# MCU.net
KiCad netlist of a schematic drawn in Altium Designer
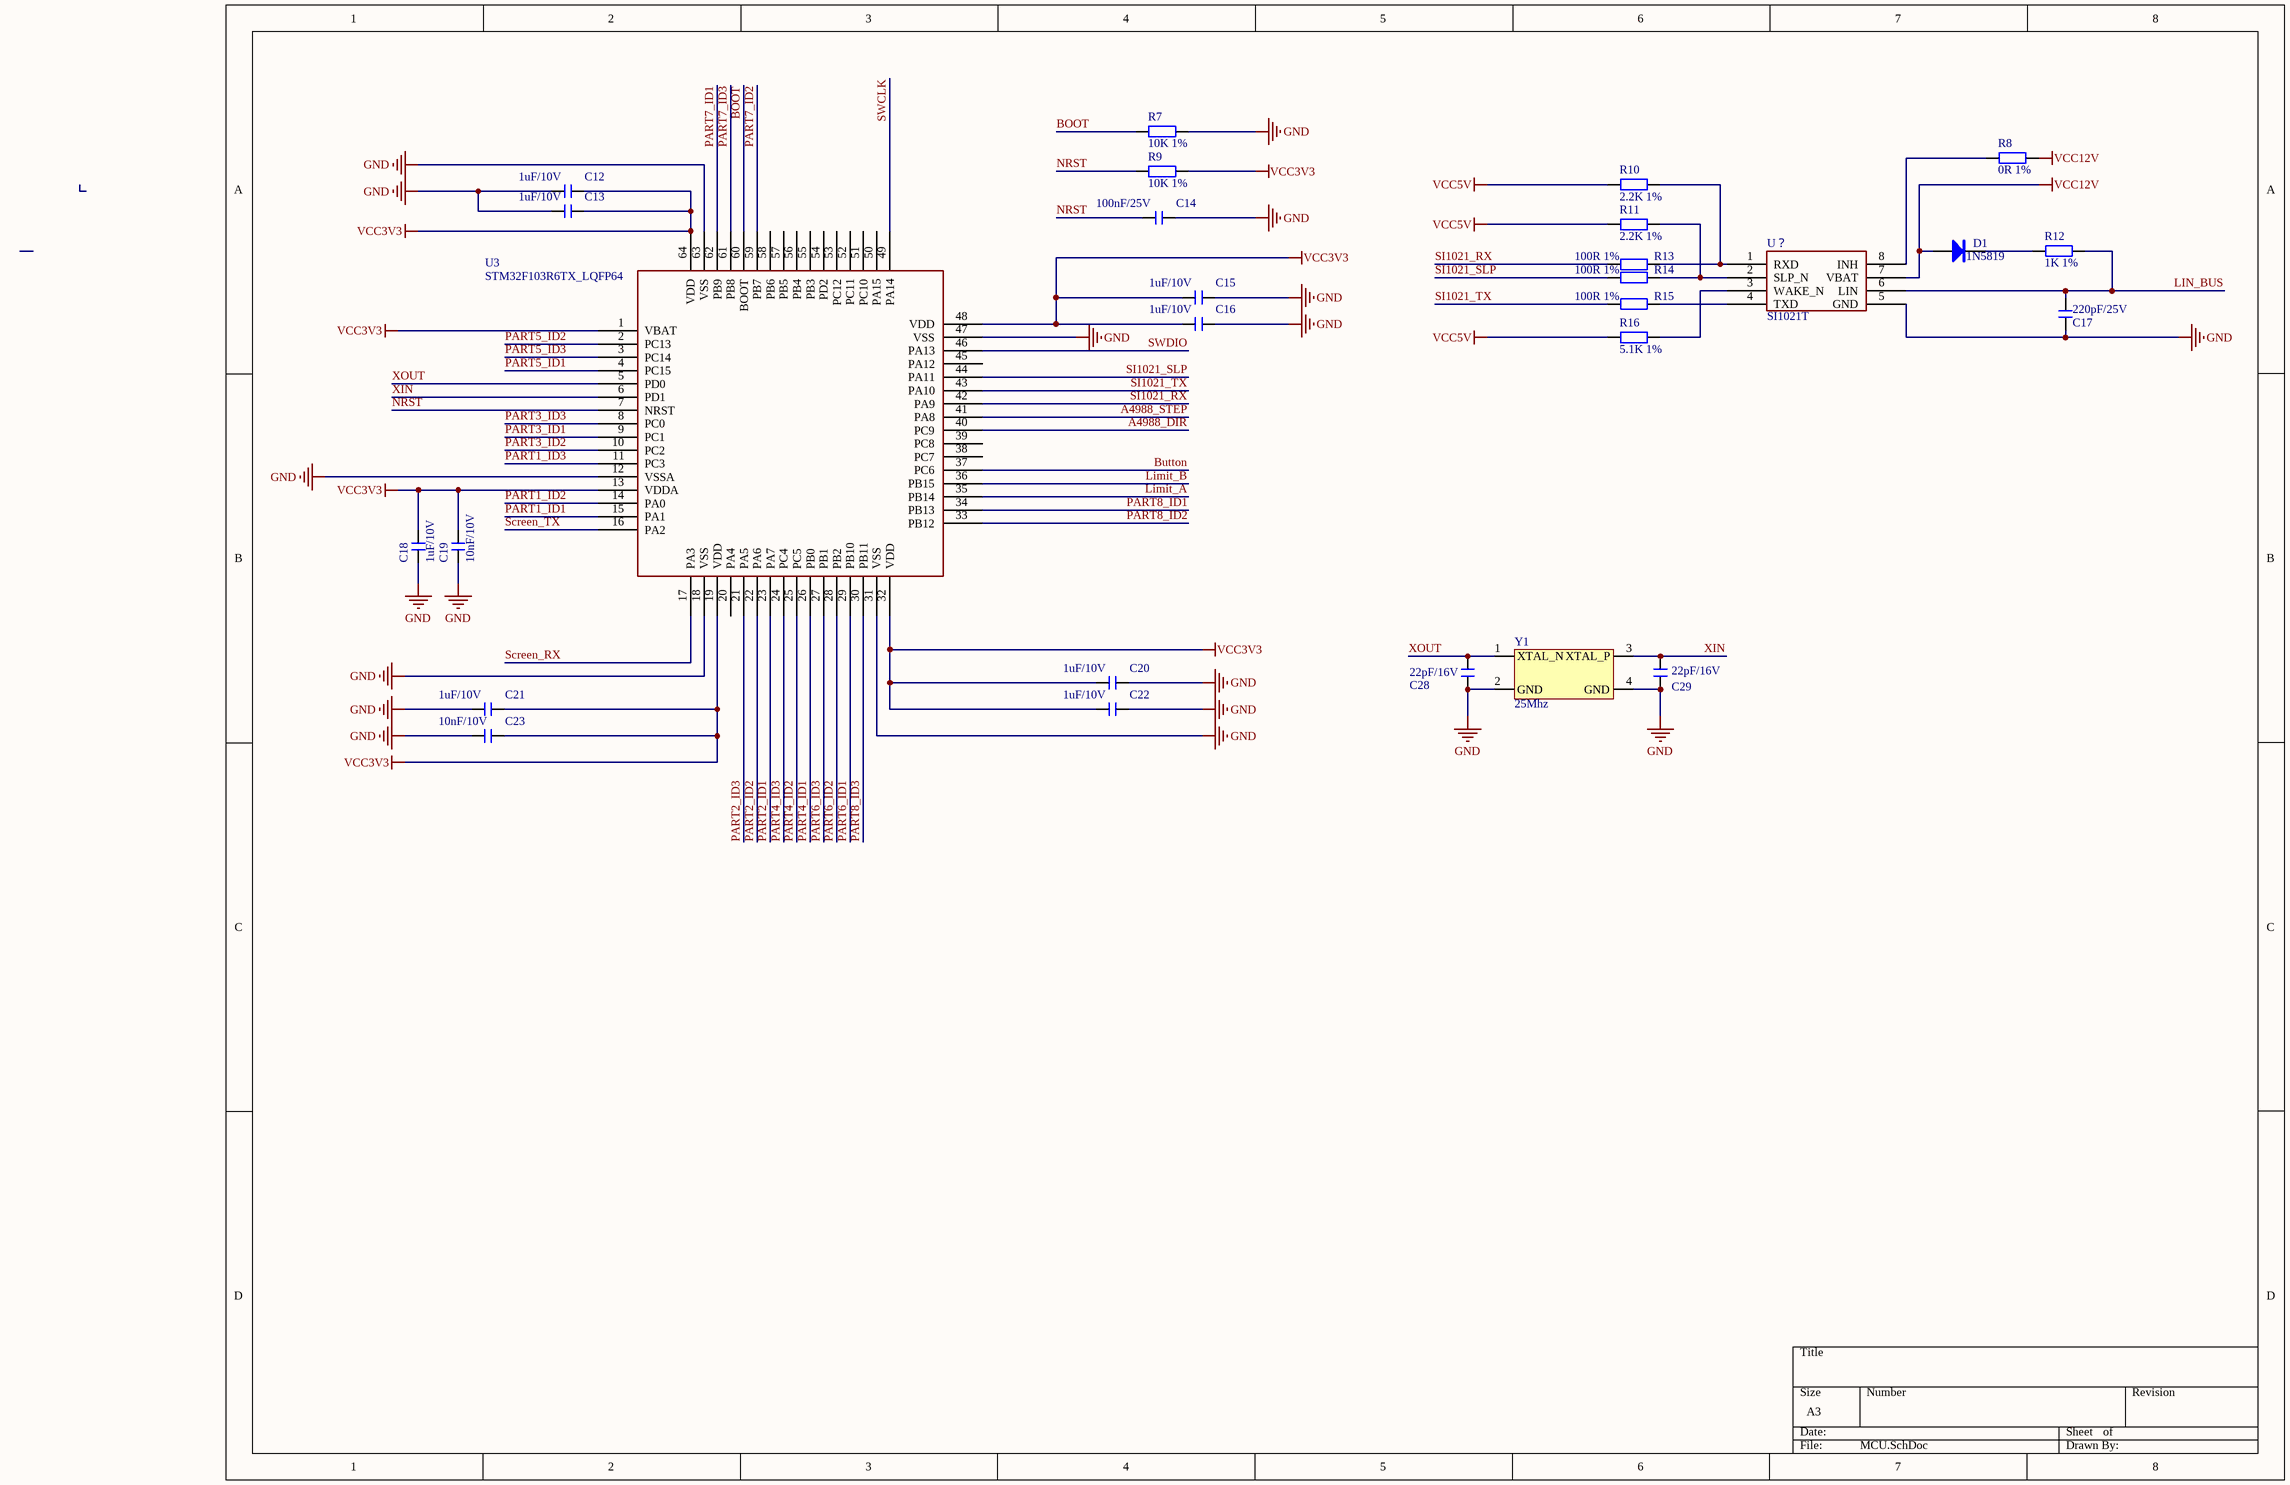
[diagram p0: MCU.SchDoc]

(export (version "E")
  (design (tool "Eeschema 10.0.6"))
  (components
    (comp (ref "C12")
      (value "1uF/10V")
      (footprint "C0603_L")
      (description "无极性贴片电容")
      (fields (field (name "版权归属") "源创客"))
      (libsource (lib "Capacitor") (part "C"))
    )
    (comp (ref "C13")
      (value "1uF/10V")
      (footprint "C0603_L")
      (description "无极性贴片电容")
      (fields (field (name "版权归属") "源创客"))
      (libsource (lib "Capacitor") (part "C"))
    )
    (comp (ref "C14")
      (value "100nF/25V")
      (footprint "C0603_L")
      (description "无极性贴片电容")
      (fields (field (name "版权归属") "源创客"))
      (libsource (lib "Capacitor") (part "C"))
    )
    (comp (ref "C15")
      (value "1uF/10V")
      (footprint "C0603_L")
      (description "无极性贴片电容")
      (fields (field (name "版权归属") "源创客"))
      (libsource (lib "Capacitor") (part "C"))
    )
    (comp (ref "C16")
      (value "1uF/10V")
      (footprint "C0603_L")
      (description "无极性贴片电容")
      (fields (field (name "版权归属") "源创客"))
      (libsource (lib "Capacitor") (part "C"))
    )
    (comp (ref "C17")
      (value "220pF/25V")
      (footprint "C0603_L")
      (description "无极性贴片电容")
      (fields (field (name "版权归属") "源创客"))
      (libsource (lib "Capacitor") (part "C"))
    )
    (comp (ref "C18")
      (value "1uF/10V")
      (footprint "C0603_L")
      (description "无极性贴片电容")
      (fields (field (name "版权归属") "源创客"))
      (libsource (lib "Capacitor") (part "C"))
    )
    (comp (ref "C19")
      (value "10nF/10V")
      (footprint "C0603_L")
      (description "无极性贴片电容")
      (fields (field (name "版权归属") "源创客"))
      (libsource (lib "Capacitor") (part "C"))
    )
    (comp (ref "C20")
      (value "1uF/10V")
      (footprint "C0603_L")
      (description "无极性贴片电容")
      (fields (field (name "版权归属") "源创客"))
      (libsource (lib "Capacitor") (part "C"))
    )
    (comp (ref "C21")
      (value "1uF/10V")
      (footprint "C0603_L")
      (description "无极性贴片电容")
      (fields (field (name "版权归属") "源创客"))
      (libsource (lib "Capacitor") (part "C"))
    )
    (comp (ref "C22")
      (value "1uF/10V")
      (footprint "C0603_L")
      (description "无极性贴片电容")
      (fields (field (name "版权归属") "源创客"))
      (libsource (lib "Capacitor") (part "C"))
    )
    (comp (ref "C23")
      (value "10nF/10V")
      (footprint "C0603_L")
      (description "无极性贴片电容")
      (fields (field (name "版权归属") "源创客"))
      (libsource (lib "Capacitor") (part "C"))
    )
    (comp (ref "C28")
      (value "22pF/16V")
      (footprint "C0402_L")
      (description "无极性贴片电容")
      (fields (field (name "版权归属") "源创客"))
      (libsource (lib "Capacitor") (part "C"))
    )
    (comp (ref "C29")
      (value "22pF/16V")
      (footprint "C0402_L")
      (description "无极性贴片电容")
      (fields (field (name "版权归属") "源创客"))
      (libsource (lib "Capacitor") (part "C"))
    )
    (comp (ref "D1")
      (value "1N5819")
      (footprint "SOD-323")
      (description "肖特基二极管")
      (fields (field (name "版权归属") "源创客"))
      (libsource (lib "Diode") (part "1N5819"))
    )
    (comp (ref "R7")
      (value "10K 1%")
      (footprint "R0603_L")
      (description "贴片电阻")
      (fields (field (name "版权归属") "源创客"))
      (libsource (lib "Resistor") (part "R"))
    )
    (comp (ref "R8")
      (value "0R 1%")
      (footprint "R0603_L")
      (description "贴片电阻")
      (fields (field (name "版权归属") "源创客"))
      (libsource (lib "Resistor") (part "R"))
    )
    (comp (ref "R9")
      (value "10K 1%")
      (footprint "R0603_L")
      (description "贴片电阻")
      (fields (field (name "版权归属") "源创客"))
      (libsource (lib "Resistor") (part "R"))
    )
    (comp (ref "R10")
      (value "2.2K 1%")
      (footprint "R0603_L")
      (description "贴片电阻")
      (fields (field (name "版权归属") "源创客"))
      (libsource (lib "Resistor") (part "R"))
    )
    (comp (ref "R11")
      (value "2.2K 1%")
      (footprint "R0603_L")
      (description "贴片电阻")
      (fields (field (name "版权归属") "源创客"))
      (libsource (lib "Resistor") (part "R"))
    )
    (comp (ref "R12")
      (value "1K 1%")
      (footprint "R0603_L")
      (description "贴片电阻")
      (fields (field (name "版权归属") "源创客"))
      (libsource (lib "Resistor") (part "R"))
    )
    (comp (ref "R13")
      (value "100R 1%")
      (footprint "R0603_L")
      (description "贴片电阻")
      (fields (field (name "版权归属") "源创客"))
      (libsource (lib "Resistor") (part "R"))
    )
    (comp (ref "R14")
      (value "100R 1%")
      (footprint "R0603_L")
      (description "贴片电阻")
      (fields (field (name "版权归属") "源创客"))
      (libsource (lib "Resistor") (part "R"))
    )
    (comp (ref "R15")
      (value "100R 1%")
      (footprint "R0603_L")
      (description "贴片电阻")
      (fields (field (name "版权归属") "源创客"))
      (libsource (lib "Resistor") (part "R"))
    )
    (comp (ref "R16")
      (value "5.1K 1%")
      (footprint "R0603_L")
      (description "贴片电阻")
      (fields (field (name "版权归属") "源创客"))
      (libsource (lib "Resistor") (part "R"))
    )
    (comp (ref "U3")
      (value "STM32F103R6TX_LQFP64")
      (footprint "LQFP64 10x10_N")
      (libsource (lib "MCU") (part "STM32F103R6TX_LQFP64"))
    )
    (comp (ref "U？")
      (value "SI1021T")
      (footprint "SOP8")
      (description "SI1021T LIN收发器")
      (libsource (lib "transceiver") (part "SI1021T"))
    )
    (comp (ref "Y1") (value "25Mhz") (footprint "OSC 3225-4P") (libsource (lib "Crystal") (part "Crystal")))
  )
  (nets
    (net (code "1") (name "/A4988_DIR") (class "Default")
      (node (ref "U3") (pin "40") (pinfunction "PC9_40") (pintype "passive"))
    )
    (net (code "2") (name "/A4988_STEP") (class "Default")
      (node (ref "U3") (pin "41") (pinfunction "PA8_41") (pintype "passive"))
    )
    (net (code "3") (name "/BOOT") (class "Default")
      (node (ref "R7") (pin "1") (pinfunction "1_1") (pintype "passive"))
      (node (ref "U3") (pin "60") (pinfunction "BOOT_60") (pintype "passive"))
    )
    (net (code "4") (name "/Button") (class "Default")
      (node (ref "U3") (pin "37") (pinfunction "PC6_37") (pintype "passive"))
    )
    (net (code "5") (name "/LIN_BUS") (class "Default")
      (node (ref "C17") (pin "2") (pinfunction "2_2") (pintype "passive"))
      (node (ref "R12") (pin "1") (pinfunction "1_1") (pintype "passive"))
      (node (ref "U？") (pin "6") (pinfunction "LIN_6") (pintype "passive"))
    )
    (net (code "6") (name "/Limit_A") (class "Default")
      (node (ref "U3") (pin "35") (pinfunction "PB14_35") (pintype "passive"))
    )
    (net (code "7") (name "/Limit_B") (class "Default")
      (node (ref "U3") (pin "36") (pinfunction "PB15_36") (pintype "passive"))
    )
    (net (code "8") (name "/NRST") (class "Default")
      (node (ref "C14") (pin "2") (pinfunction "2_2") (pintype "passive"))
      (node (ref "R9") (pin "1") (pinfunction "1_1") (pintype "passive"))
      (node (ref "U3") (pin "7") (pinfunction "NRST_7") (pintype "passive"))
    )
    (net (code "9") (name "/PART1_ID1") (class "Default")
      (node (ref "U3") (pin "15") (pinfunction "PA1_15") (pintype "passive"))
    )
    (net (code "10") (name "/PART1_ID2") (class "Default")
      (node (ref "U3") (pin "14") (pinfunction "PA0_14") (pintype "passive"))
    )
    (net (code "11") (name "/PART1_ID3") (class "Default")
      (node (ref "U3") (pin "11") (pinfunction "PC3_11") (pintype "passive"))
    )
    (net (code "12") (name "/PART2_ID1") (class "Default")
      (node (ref "U3") (pin "23") (pinfunction "PA7_23") (pintype "passive"))
    )
    (net (code "13") (name "/PART2_ID2") (class "Default")
      (node (ref "U3") (pin "22") (pinfunction "PA6_22") (pintype "passive"))
    )
    (net (code "14") (name "/PART2_ID3") (class "Default")
      (node (ref "U3") (pin "21") (pinfunction "PA5_21") (pintype "passive"))
    )
    (net (code "15") (name "/PART3_ID1") (class "Default")
      (node (ref "U3") (pin "9") (pinfunction "PC1_9") (pintype "passive"))
    )
    (net (code "16") (name "/PART3_ID2") (class "Default")
      (node (ref "U3") (pin "10") (pinfunction "PC2_10") (pintype "passive"))
    )
    (net (code "17") (name "/PART3_ID3") (class "Default")
      (node (ref "U3") (pin "8") (pinfunction "PC0_8") (pintype "passive"))
    )
    (net (code "18") (name "/PART4_ID1") (class "Default")
      (node (ref "U3") (pin "26") (pinfunction "PB0_26") (pintype "passive"))
    )
    (net (code "19") (name "/PART4_ID2") (class "Default")
      (node (ref "U3") (pin "25") (pinfunction "PC5_25") (pintype "passive"))
    )
    (net (code "20") (name "/PART4_ID3") (class "Default")
      (node (ref "U3") (pin "24") (pinfunction "PC4_24") (pintype "passive"))
    )
    (net (code "21") (name "/PART5_ID1") (class "Default")
      (node (ref "U3") (pin "4") (pinfunction "PC15_4") (pintype "passive"))
    )
    (net (code "22") (name "/PART5_ID2") (class "Default")
      (node (ref "U3") (pin "2") (pinfunction "PC13_2") (pintype "passive"))
    )
    (net (code "23") (name "/PART5_ID3") (class "Default")
      (node (ref "U3") (pin "3") (pinfunction "PC14_3") (pintype "passive"))
    )
    (net (code "24") (name "/PART6_ID1") (class "Default")
      (node (ref "U3") (pin "29") (pinfunction "PB10_29") (pintype "passive"))
    )
    (net (code "25") (name "/PART6_ID2") (class "Default")
      (node (ref "U3") (pin "28") (pinfunction "PB2_28") (pintype "passive"))
    )
    (net (code "26") (name "/PART6_ID3") (class "Default")
      (node (ref "U3") (pin "27") (pinfunction "PB1_27") (pintype "passive"))
    )
    (net (code "27") (name "/PART7_ID1") (class "Default")
      (node (ref "U3") (pin "62") (pinfunction "PB9_62") (pintype "passive"))
    )
    (net (code "28") (name "/PART7_ID2") (class "Default")
      (node (ref "U3") (pin "59") (pinfunction "PB7_59") (pintype "passive"))
    )
    (net (code "29") (name "/PART7_ID3") (class "Default")
      (node (ref "U3") (pin "61") (pinfunction "PB8_61") (pintype "passive"))
    )
    (net (code "30") (name "/PART8_ID1") (class "Default")
      (node (ref "U3") (pin "34") (pinfunction "PB13_34") (pintype "passive"))
    )
    (net (code "31") (name "/PART8_ID2") (class "Default")
      (node (ref "U3") (pin "33") (pinfunction "PB12_33") (pintype "passive"))
    )
    (net (code "32") (name "/PART8_ID3") (class "Default")
      (node (ref "U3") (pin "30") (pinfunction "PB11_30") (pintype "passive"))
    )
    (net (code "33") (name "/SI1021_RX") (class "Default")
      (node (ref "R13") (pin "1") (pinfunction "1_1") (pintype "passive"))
      (node (ref "U3") (pin "42") (pinfunction "PA9_42") (pintype "passive"))
    )
    (net (code "34") (name "/SI1021_SLP") (class "Default")
      (node (ref "R14") (pin "1") (pinfunction "1_1") (pintype "passive"))
      (node (ref "U3") (pin "44") (pinfunction "PA11_44") (pintype "passive"))
    )
    (net (code "35") (name "/SI1021_TX") (class "Default")
      (node (ref "R15") (pin "1") (pinfunction "1_1") (pintype "passive"))
      (node (ref "U3") (pin "43") (pinfunction "PA10_43") (pintype "passive"))
    )
    (net (code "36") (name "/SWCLK") (class "Default")
      (node (ref "U3") (pin "49") (pinfunction "PA14_49") (pintype "passive"))
    )
    (net (code "37") (name "/SWDIO") (class "Default")
      (node (ref "U3") (pin "46") (pinfunction "PA13_46") (pintype "passive"))
    )
    (net (code "38") (name "/Screen_RX") (class "Default")
      (node (ref "U3") (pin "17") (pinfunction "PA3_17") (pintype "passive"))
    )
    (net (code "39") (name "/Screen_TX") (class "Default")
      (node (ref "U3") (pin "16") (pinfunction "PA2_16") (pintype "passive"))
    )
    (net (code "40") (name "/XIN") (class "Default")
      (node (ref "C29") (pin "1") (pinfunction "1_1") (pintype "passive"))
      (node (ref "U3") (pin "6") (pinfunction "PD1_6") (pintype "passive"))
      (node (ref "Y1") (pin "3") (pinfunction "XTAL_P_3") (pintype "passive"))
    )
    (net (code "41") (name "/XOUT") (class "Default")
      (node (ref "C28") (pin "1") (pinfunction "1_1") (pintype "passive"))
      (node (ref "U3") (pin "5") (pinfunction "PD0_5") (pintype "passive"))
      (node (ref "Y1") (pin "1") (pinfunction "XTAL_N_1") (pintype "passive"))
    )
    (net (code "42") (name "GND") (class "Default")
      (node (ref "C12") (pin "2") (pinfunction "2_2") (pintype "passive"))
      (node (ref "C13") (pin "2") (pinfunction "2_2") (pintype "passive"))
      (node (ref "C14") (pin "1") (pinfunction "1_1") (pintype "passive"))
      (node (ref "C15") (pin "1") (pinfunction "1_1") (pintype "passive"))
      (node (ref "C16") (pin "1") (pinfunction "1_1") (pintype "passive"))
      (node (ref "C17") (pin "1") (pinfunction "1_1") (pintype "passive"))
      (node (ref "C18") (pin "1") (pinfunction "1_1") (pintype "passive"))
      (node (ref "C19") (pin "1") (pinfunction "1_1") (pintype "passive"))
      (node (ref "C20") (pin "1") (pinfunction "1_1") (pintype "passive"))
      (node (ref "C21") (pin "2") (pinfunction "2_2") (pintype "passive"))
      (node (ref "C22") (pin "1") (pinfunction "1_1") (pintype "passive"))
      (node (ref "C23") (pin "2") (pinfunction "2_2") (pintype "passive"))
      (node (ref "C28") (pin "2") (pinfunction "2_2") (pintype "passive"))
      (node (ref "C29") (pin "2") (pinfunction "2_2") (pintype "passive"))
      (node (ref "R7") (pin "2") (pinfunction "2_2") (pintype "passive"))
      (node (ref "U3") (pin "12") (pinfunction "VSSA_12") (pintype "passive"))
      (node (ref "U3") (pin "18") (pinfunction "VSS_18") (pintype "passive"))
      (node (ref "U3") (pin "31") (pinfunction "VSS_31") (pintype "passive"))
      (node (ref "U3") (pin "47") (pinfunction "VSS_47") (pintype "passive"))
      (node (ref "U3") (pin "63") (pinfunction "VSS_63") (pintype "passive"))
      (node (ref "U？") (pin "5") (pinfunction "GND_5") (pintype "passive"))
      (node (ref "Y1") (pin "2") (pinfunction "GND_2") (pintype "passive"))
      (node (ref "Y1") (pin "4") (pinfunction "GND_4") (pintype "passive"))
    )
    (net (code "43") (name "Net-(D1-K)") (class "Default")
      (node (ref "D1") (pin "2") (pinfunction "K_2") (pintype "passive"))
      (node (ref "R12") (pin "2") (pinfunction "2_2") (pintype "passive"))
    )
    (net (code "44") (name "Net-(U？-INH)") (class "Default")
      (node (ref "R8") (pin "2") (pinfunction "2_2") (pintype "passive"))
      (node (ref "U？") (pin "8") (pinfunction "INH_8") (pintype "passive"))
    )
    (net (code "45") (name "Net-(U？-RXD)") (class "Default")
      (node (ref "R10") (pin "1") (pinfunction "1_1") (pintype "passive"))
      (node (ref "R13") (pin "2") (pinfunction "2_2") (pintype "passive"))
      (node (ref "U？") (pin "1") (pinfunction "RXD_1") (pintype "passive"))
    )
    (net (code "46") (name "Net-(U？-SLP_N)") (class "Default")
      (node (ref "R11") (pin "1") (pinfunction "1_1") (pintype "passive"))
      (node (ref "R14") (pin "2") (pinfunction "2_2") (pintype "passive"))
      (node (ref "U？") (pin "2") (pinfunction "SLP_N_2") (pintype "passive"))
    )
    (net (code "47") (name "Net-(U？-TXD)") (class "Default")
      (node (ref "R15") (pin "2") (pinfunction "2_2") (pintype "passive"))
      (node (ref "U？") (pin "4") (pinfunction "TXD_4") (pintype "passive"))
    )
    (net (code "48") (name "Net-(U？-WAKE_N)") (class "Default")
      (node (ref "R16") (pin "1") (pinfunction "1_1") (pintype "passive"))
      (node (ref "U？") (pin "3") (pinfunction "WAKE_N_3") (pintype "passive"))
    )
    (net (code "49") (name "VCC3V3") (class "Default")
      (node (ref "C12") (pin "1") (pinfunction "1_1") (pintype "passive"))
      (node (ref "C13") (pin "1") (pinfunction "1_1") (pintype "passive"))
      (node (ref "C15") (pin "2") (pinfunction "2_2") (pintype "passive"))
      (node (ref "C16") (pin "2") (pinfunction "2_2") (pintype "passive"))
      (node (ref "C18") (pin "2") (pinfunction "2_2") (pintype "passive"))
      (node (ref "C19") (pin "2") (pinfunction "2_2") (pintype "passive"))
      (node (ref "C20") (pin "2") (pinfunction "2_2") (pintype "passive"))
      (node (ref "C21") (pin "1") (pinfunction "1_1") (pintype "passive"))
      (node (ref "C22") (pin "2") (pinfunction "2_2") (pintype "passive"))
      (node (ref "C23") (pin "1") (pinfunction "1_1") (pintype "passive"))
      (node (ref "R9") (pin "2") (pinfunction "2_2") (pintype "passive"))
      (node (ref "U3") (pin "1") (pinfunction "VBAT_1") (pintype "passive"))
      (node (ref "U3") (pin "13") (pinfunction "VDDA_13") (pintype "passive"))
      (node (ref "U3") (pin "19") (pinfunction "VDD_19") (pintype "passive"))
      (node (ref "U3") (pin "32") (pinfunction "VDD_32") (pintype "passive"))
      (node (ref "U3") (pin "48") (pinfunction "VDD_48") (pintype "passive"))
      (node (ref "U3") (pin "64") (pinfunction "VDD_64") (pintype "passive"))
    )
    (net (code "50") (name "VCC5V") (class "Default")
      (node (ref "R10") (pin "2") (pinfunction "2_2") (pintype "passive"))
      (node (ref "R11") (pin "2") (pinfunction "2_2") (pintype "passive"))
      (node (ref "R16") (pin "2") (pinfunction "2_2") (pintype "passive"))
    )
    (net (code "51") (name "VCC12V") (class "Default")
      (node (ref "D1") (pin "1") (pinfunction "A_1") (pintype "passive"))
      (node (ref "R8") (pin "1") (pinfunction "1_1") (pintype "passive"))
      (node (ref "U？") (pin "7") (pinfunction "VBAT_7") (pintype "passive"))
    )
    (net (code "52") (name "unconnected-(U3-PA4-Pad20)") (class "Default")
      (node (ref "U3") (pin "20") (pinfunction "PA4_20") (pintype "passive"))
    )
    (net (code "53") (name "unconnected-(U3-PA12-Pad45)") (class "Default")
      (node (ref "U3") (pin "45") (pinfunction "PA12_45") (pintype "passive"))
    )
    (net (code "54") (name "unconnected-(U3-PA15-Pad50)") (class "Default")
      (node (ref "U3") (pin "50") (pinfunction "PA15_50") (pintype "passive"))
    )
    (net (code "55") (name "unconnected-(U3-PB3-Pad55)") (class "Default")
      (node (ref "U3") (pin "55") (pinfunction "PB3_55") (pintype "passive"))
    )
    (net (code "56") (name "unconnected-(U3-PB4-Pad56)") (class "Default")
      (node (ref "U3") (pin "56") (pinfunction "PB4_56") (pintype "passive"))
    )
    (net (code "57") (name "unconnected-(U3-PB5-Pad57)") (class "Default")
      (node (ref "U3") (pin "57") (pinfunction "PB5_57") (pintype "passive"))
    )
    (net (code "58") (name "unconnected-(U3-PB6-Pad58)") (class "Default")
      (node (ref "U3") (pin "58") (pinfunction "PB6_58") (pintype "passive"))
    )
    (net (code "59") (name "unconnected-(U3-PC7-Pad38)") (class "Default")
      (node (ref "U3") (pin "38") (pinfunction "PC7_38") (pintype "passive"))
    )
    (net (code "60") (name "unconnected-(U3-PC8-Pad39)") (class "Default")
      (node (ref "U3") (pin "39") (pinfunction "PC8_39") (pintype "passive"))
    )
    (net (code "61") (name "unconnected-(U3-PC10-Pad51)") (class "Default")
      (node (ref "U3") (pin "51") (pinfunction "PC10_51") (pintype "passive"))
    )
    (net (code "62") (name "unconnected-(U3-PC11-Pad52)") (class "Default")
      (node (ref "U3") (pin "52") (pinfunction "PC11_52") (pintype "passive"))
    )
    (net (code "63") (name "unconnected-(U3-PC12-Pad53)") (class "Default")
      (node (ref "U3") (pin "53") (pinfunction "PC12_53") (pintype "passive"))
    )
    (net (code "64") (name "unconnected-(U3-PD2-Pad54)") (class "Default")
      (node (ref "U3") (pin "54") (pinfunction "PD2_54") (pintype "passive"))
    )
  )
)
